# 04_ElectronicScales.net
KiCad netlist of a schematic drawn in Altium Designer
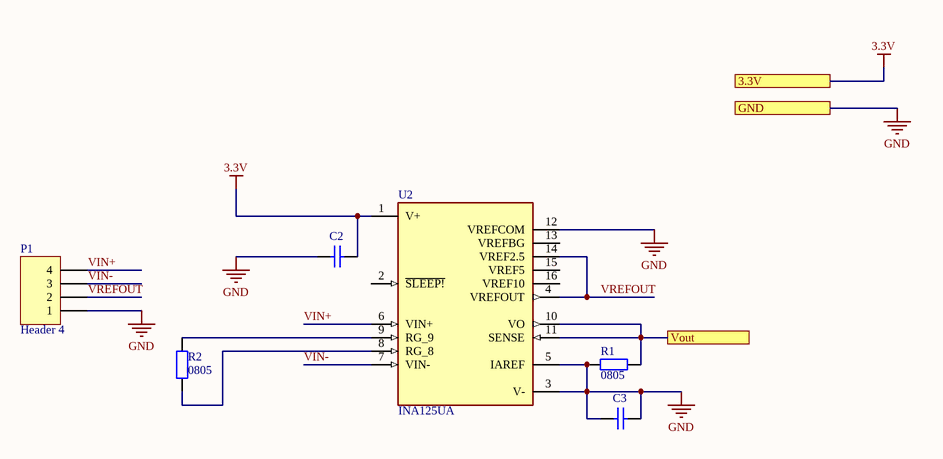
[diagram p0: 04_ElectronicScales.SchDoc]

(export (version "E")
  (design (tool "Eeschema 10.0.6"))
  (components
    (comp (ref "C2")
      (value "Capacitor Ceramic")
      (footprint "C0805")
      (description "Capacitor")
      (fields (field (name "PUBLISHER") "Altium Limited"))
      (libsource (lib "My Library") (part "CapSMD"))
    )
    (comp (ref "C3")
      (value "Capacitor Ceramic")
      (footprint "C0805")
      (description "Capacitor")
      (fields (field (name "PUBLISHER") "Altium Limited"))
      (libsource (lib "My Library") (part "CapSMD"))
    )
    (comp (ref "P1")
      (value "Header 4")
      (footprint "HDR1X4")
      (description "Header, 4-Pin")
      (fields (field (name "PUBLISHER") "Altium Limited"))
      (libsource (lib "My Library") (part "Header 4"))
    )
    (comp (ref "R1")
      (value "0805")
      (footprint "DIEN TRO 0805")
      (description "Resistor SMD 0805")
      (fields (field (name "Comment") "R0805") (field (name "PUBLISHER") "Altium Limited"))
      (libsource (lib "") (part "R0805_1"))
    )
    (comp (ref "R2")
      (value "0805")
      (footprint "DIEN TRO 0805")
      (description "Resistor SMD 0805")
      (fields (field (name "Comment") "R0805") (field (name "PUBLISHER") "Altium Limited"))
      (libsource (lib "My Library") (part "R0805"))
    )
    (comp (ref "U2")
      (value "INA125UA")
      (footprint "SOIC127P600X175-16N")
      (description "Instrumentation Amplifier with Precision Voltage Reference 16-SOIC")
      (libsource (lib "INA125UA") (part "INA125UA"))
    )
  )
  (nets
    (net (code "1") (name "/VIN+") (class "Default")
      (node (ref "P1") (pin "4") (pinfunction "4_4") (pintype "passive"))
      (node (ref "U2") (pin "6") (pinfunction "VIN+_6") (pintype "input"))
    )
    (net (code "2") (name "/VIN-") (class "Default")
      (node (ref "P1") (pin "3") (pinfunction "3_3") (pintype "passive"))
      (node (ref "U2") (pin "7") (pinfunction "VIN-_7") (pintype "input"))
    )
    (net (code "3") (name "/VREFOUT") (class "Default")
      (node (ref "P1") (pin "2") (pinfunction "2_2") (pintype "passive"))
      (node (ref "U2") (pin "14") (pinfunction "VREF2.5_14") (pintype "passive"))
      (node (ref "U2") (pin "4") (pinfunction "VREFOUT_4") (pintype "output"))
    )
    (net (code "4") (name "/Vout") (class "Default")
      (node (ref "R1") (pin "1") (pinfunction "1_1") (pintype "passive"))
      (node (ref "U2") (pin "10") (pinfunction "VO_10") (pintype "output"))
      (node (ref "U2") (pin "11") (pinfunction "SENSE_11") (pintype "input"))
    )
    (net (code "5") (name "3.3V") (class "Default")
      (node (ref "C2") (pin "2") (pinfunction "2_2") (pintype "passive"))
      (node (ref "U2") (pin "1") (pinfunction "V+_1") (pintype "power_in"))
    )
    (net (code "6") (name "GND") (class "Default")
      (node (ref "C2") (pin "1") (pinfunction "1_1") (pintype "passive"))
      (node (ref "C3") (pin "1") (pinfunction "1_1") (pintype "passive"))
      (node (ref "C3") (pin "2") (pinfunction "2_2") (pintype "passive"))
      (node (ref "P1") (pin "1") (pinfunction "1_1") (pintype "passive"))
      (node (ref "R1") (pin "2") (pinfunction "2_2") (pintype "passive"))
      (node (ref "U2") (pin "12") (pinfunction "VREFCOM_12") (pintype "passive"))
      (node (ref "U2") (pin "3") (pinfunction "V-_3") (pintype "power_in"))
      (node (ref "U2") (pin "5") (pinfunction "IAREF_5") (pintype "passive"))
    )
    (net (code "7") (name "Net-(U2-RG_8)") (class "Default")
      (node (ref "R2") (pin "1") (pinfunction "1_1") (pintype "passive"))
      (node (ref "U2") (pin "8") (pinfunction "RG_8_8") (pintype "input"))
    )
    (net (code "8") (name "Net-(U2-RG_9)") (class "Default")
      (node (ref "R2") (pin "2") (pinfunction "2_2") (pintype "passive"))
      (node (ref "U2") (pin "9") (pinfunction "RG_9_9") (pintype "input"))
    )
    (net (code "9") (name "unconnected-(U2-VREF5-Pad15)") (class "Default")
      (node (ref "U2") (pin "15") (pinfunction "VREF5_15") (pintype "passive"))
    )
    (net (code "10") (name "unconnected-(U2-VREF10-Pad16)") (class "Default")
      (node (ref "U2") (pin "16") (pinfunction "VREF10_16") (pintype "passive"))
    )
    (net (code "11") (name "unconnected-(U2-VREFBG-Pad13)") (class "Default")
      (node (ref "U2") (pin "13") (pinfunction "VREFBG_13") (pintype "passive"))
    )
    (net (code "12") (name "unconnected-(U2-~{SLEEP!}-Pad2)") (class "Default")
      (node (ref "U2") (pin "2") (pinfunction "~{SLEEP!}_2") (pintype "input"))
    )
  )
)
